# main.net
KiCad netlist of a schematic drawn in Altium Designer
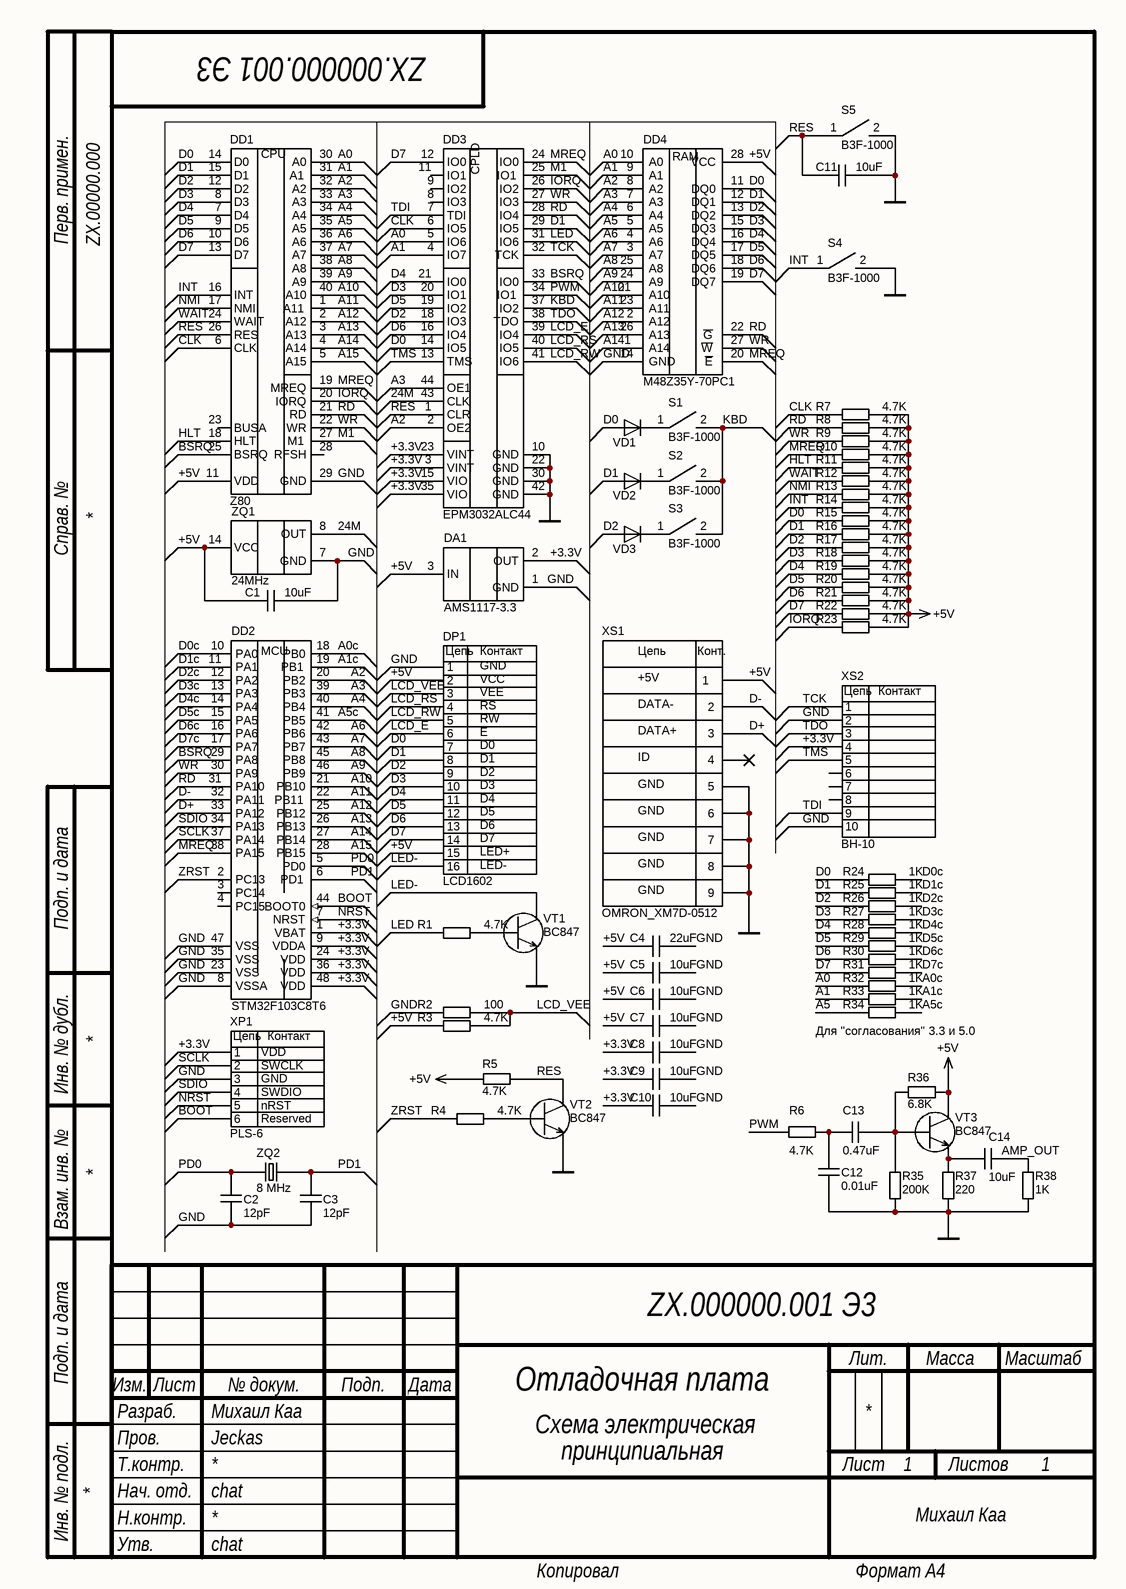
[diagram p0: main.SchDoc]

(export (version "E")
  (design (tool "Eeschema 10.0.6"))
  (components
    (comp (ref "C1") (value "10uF") (footprint "C0805") (libsource (lib "Capacitors") (part "CapCer")))
    (comp (ref "C2") (value "12pF") (footprint "C0805") (libsource (lib "Capacitors") (part "CapCer")))
    (comp (ref "C3") (value "12pF") (footprint "C0805") (libsource (lib "Capacitors") (part "CapCer")))
    (comp (ref "C4") (value "22uF") (footprint "С1206") (libsource (lib "Capacitors") (part "CapCer")))
    (comp (ref "C5") (value "10uF") (footprint "C0805") (libsource (lib "Capacitors") (part "CapCer")))
    (comp (ref "C6") (value "10uF") (footprint "C0805") (libsource (lib "Capacitors") (part "CapCer")))
    (comp (ref "C7") (value "10uF") (footprint "C0805") (libsource (lib "Capacitors") (part "CapCer")))
    (comp (ref "C8") (value "10uF") (footprint "C0805") (libsource (lib "Capacitors") (part "CapCer")))
    (comp (ref "C9") (value "10uF") (footprint "C0805") (libsource (lib "Capacitors") (part "CapCer")))
    (comp (ref "C10") (value "10uF") (footprint "C0805") (libsource (lib "Capacitors") (part "CapCer")))
    (comp (ref "C11") (value "10uF") (footprint "C0805") (libsource (lib "Capacitors") (part "CapCer")))
    (comp (ref "C12") (value "0.01uF") (footprint "C0805") (libsource (lib "Capacitors") (part "CapCer")))
    (comp (ref "C13") (value "0.47uF") (footprint "C0805") (libsource (lib "Capacitors") (part "CapCer")))
    (comp (ref "C14") (value "10uF") (footprint "C0805") (libsource (lib "Capacitors") (part "CapCer")))
    (comp (ref "DA1")
      (value "AMS1117-3.3")
      (footprint "SOT229P700X180-4N")
      (libsource (lib "LDO") (part "AMS1117-3.3"))
    )
    (comp (ref "DD1")
      (value "Z80")
      (footprint "DIP1540W47P254L5320H635Q40B")
      (libsource (lib "Z80") (part "Z80"))
    )
    (comp (ref "DD2")
      (value "STM32F103C8T6")
      (footprint "QFP50P900X900X160-48N")
      (description "ARMÂ® CortexÂ®-M3 STM32F1 Microcontroller IC 32-Bit 72MHz 64KB (64K x 8) FLASH 48-LQFP (7x7)")
      (fields (field (name "MF") "STMicroelectronics"))
      (libsource (lib "MCU") (part "STM32F103C8T6"))
    )
    (comp (ref "DD3")
      (value "EPM3032ALC44")
      (footprint "PLCC-44-R")
      (description "44-Pin PLCC44")
      (libsource (lib "cpld") (part "EPM3032ALC44"))
    )
    (comp (ref "DD4")
      (value "M48Z35Y-70PC1")
      (footprint "DIP254P1524X965-28")
      (description "NVSRAM (Non-Volatile SRAM) Memory IC 256Kb (32K x 8) Parallel 70ns 28-PCDIP, CAPHATÂ®")
      (fields (field (name "MF") "STMicroelectronics"))
      (libsource (lib "RAM") (part "M48Z35Y-70PC1"))
    )
    (comp (ref "DP1") (value "LCD1602") (footprint "LCD1602") (libsource (lib "Display") (part "LCD1602")))
    (comp (ref "R1") (value "4.7K") (footprint "R0805") (libsource (lib "Resistors") (part "Res")))
    (comp (ref "R2") (value "100") (footprint "R0805") (libsource (lib "Resistors") (part "Res")))
    (comp (ref "R3") (value "4.7K") (footprint "R0805") (libsource (lib "Resistors") (part "Res")))
    (comp (ref "R4") (value "4.7K") (footprint "R0805") (libsource (lib "Resistors") (part "Res")))
    (comp (ref "R5") (value "4.7K") (footprint "R0805") (libsource (lib "Resistors") (part "Res")))
    (comp (ref "R6") (value "4.7K") (footprint "R0805") (libsource (lib "Resistors") (part "Res")))
    (comp (ref "R7") (value "4.7K") (footprint "R0805") (libsource (lib "Resistors") (part "Res")))
    (comp (ref "R8") (value "4.7K") (footprint "R0805") (libsource (lib "Resistors") (part "Res")))
    (comp (ref "R9") (value "4.7K") (footprint "R0805") (libsource (lib "Resistors") (part "Res")))
    (comp (ref "R10") (value "4.7K") (footprint "R0805") (libsource (lib "Resistors") (part "Res")))
    (comp (ref "R11") (value "4.7K") (footprint "R0805") (libsource (lib "Resistors") (part "Res")))
    (comp (ref "R12") (value "4.7K") (footprint "R0805") (libsource (lib "Resistors") (part "Res")))
    (comp (ref "R13") (value "4.7K") (footprint "R0805") (libsource (lib "Resistors") (part "Res")))
    (comp (ref "R14") (value "4.7K") (footprint "R0805") (libsource (lib "Resistors") (part "Res")))
    (comp (ref "R15") (value "4.7K") (footprint "R0805") (libsource (lib "Resistors") (part "Res")))
    (comp (ref "R16") (value "4.7K") (footprint "R0805") (libsource (lib "Resistors") (part "Res")))
    (comp (ref "R17") (value "4.7K") (footprint "R0805") (libsource (lib "Resistors") (part "Res")))
    (comp (ref "R18") (value "4.7K") (footprint "R0805") (libsource (lib "Resistors") (part "Res")))
    (comp (ref "R19") (value "4.7K") (footprint "R0805") (libsource (lib "Resistors") (part "Res")))
    (comp (ref "R20") (value "4.7K") (footprint "R0805") (libsource (lib "Resistors") (part "Res")))
    (comp (ref "R21") (value "4.7K") (footprint "R0805") (libsource (lib "Resistors") (part "Res")))
    (comp (ref "R22") (value "4.7K") (footprint "R0805") (libsource (lib "Resistors") (part "Res")))
    (comp (ref "R23") (value "4.7K") (footprint "R0805") (libsource (lib "Resistors") (part "Res")))
    (comp (ref "R24") (value "1K") (footprint "R0805") (libsource (lib "Resistors") (part "Res")))
    (comp (ref "R25") (value "1K") (footprint "R0805") (libsource (lib "Resistors") (part "Res")))
    (comp (ref "R26") (value "1K") (footprint "R0805") (libsource (lib "Resistors") (part "Res")))
    (comp (ref "R27") (value "1K") (footprint "R0805") (libsource (lib "Resistors") (part "Res")))
    (comp (ref "R28") (value "1K") (footprint "R0805") (libsource (lib "Resistors") (part "Res")))
    (comp (ref "R29") (value "1K") (footprint "R0805") (libsource (lib "Resistors") (part "Res")))
    (comp (ref "R30") (value "1K") (footprint "R0805") (libsource (lib "Resistors") (part "Res")))
    (comp (ref "R31") (value "1K") (footprint "R0805") (libsource (lib "Resistors") (part "Res")))
    (comp (ref "R32") (value "1K") (footprint "R0805") (libsource (lib "Resistors") (part "Res")))
    (comp (ref "R33") (value "1K") (footprint "R0805") (libsource (lib "Resistors") (part "Res")))
    (comp (ref "R34") (value "1K") (footprint "R0805") (libsource (lib "Resistors") (part "Res")))
    (comp (ref "R35") (value "200K") (footprint "R0805") (libsource (lib "Resistors") (part "Res")))
    (comp (ref "R36") (value "6.8K") (footprint "R0805") (libsource (lib "Resistors") (part "Res")))
    (comp (ref "R37") (value "220") (footprint "R0805") (libsource (lib "Resistors") (part "Res")))
    (comp (ref "R38") (value "1K") (footprint "R0805") (libsource (lib "Resistors") (part "Res")))
    (comp (ref "S1")
      (value "B3F-1000")
      (footprint "SW_B3F-1000")
      (libsource (lib "Buttons") (part "B3F-1000"))
    )
    (comp (ref "S2")
      (value "B3F-1000")
      (footprint "SW_B3F-1000")
      (libsource (lib "Buttons") (part "B3F-1000"))
    )
    (comp (ref "S3")
      (value "B3F-1000")
      (footprint "SW_B3F-1000")
      (libsource (lib "Buttons") (part "B3F-1000"))
    )
    (comp (ref "S4")
      (value "B3F-1000")
      (footprint "SW_B3F-1000")
      (libsource (lib "Buttons") (part "B3F-1000"))
    )
    (comp (ref "S5")
      (value "B3F-1000")
      (footprint "SW_B3F-1000")
      (libsource (lib "Buttons") (part "B3F-1000"))
    )
    (comp (ref "VD1")
      (value "1N4148W")
      (footprint "SODFL1608X70N")
      (libsource (lib "Diodes") (part "1N4148W"))
    )
    (comp (ref "VD2")
      (value "1N4148W")
      (footprint "SODFL1608X70N")
      (libsource (lib "Diodes") (part "1N4148W"))
    )
    (comp (ref "VD3")
      (value "1N4148W")
      (footprint "SODFL1608X70N")
      (libsource (lib "Diodes") (part "1N4148W"))
    )
    (comp (ref "VT1")
      (value "BC847")
      (footprint "BC847")
      (description "NPN Transistor")
      (libsource (lib "Transistors") (part "BC847"))
    )
    (comp (ref "VT2")
      (value "BC847")
      (footprint "BC847")
      (description "NPN Transistor")
      (libsource (lib "Transistors") (part "BC847"))
    )
    (comp (ref "VT3")
      (value "BC847")
      (footprint "BC847")
      (description "NPN Transistor")
      (libsource (lib "Transistors") (part "BC847"))
    )
    (comp (ref "XP1") (value "PLS-6") (footprint "6pin") (libsource (lib "Connectors") (part "PLS-6")))
    (comp (ref "XS1")
      (value "OMRON_XM7D-0512")
      (footprint "OMRON_XM7D-0512")
      (libsource (lib "Connectors") (part "OMRON_XM7D-0512"))
    )
    (comp (ref "XS2")
      (value "BH-10")
      (footprint "BH-10")
      (description "10 Position Total Dual Row 2.54 mm Pitch Straight Male Shrouded Box Header")
      (fields (field (name "MF") "Sullins Connector") (field (name "MP") "SBH11-PBPC-D05-ST-BK"))
      (libsource (lib "Connectors") (part "BH-10"))
    )
    (comp (ref "ZQ1")
      (value "24MHz")
      (footprint "OSC_ECS-100A-240")
      (description "Oscillator  14-DIP, 4 Leads (Full Size, Metal Can)")
      (fields (field (name "MP") "ECS-100A-240"))
      (libsource (lib "Oscillators") (part "ECS-100A-240"))
    )
    (comp (ref "ZQ2")
      (value "8 MHz")
      (footprint "XTAL_ECS-80-S-4")
      (libsource (lib "Oscillators") (part "HC-49S_8M"))
    )
  )
  (nets
    (net (code "1") (name "+5V") (class "Default")
      (node (ref "C1") (pin "1") (pinfunction "1_1") (pintype "passive"))
      (node (ref "C4") (pin "1") (pinfunction "1_1") (pintype "passive"))
      (node (ref "C5") (pin "1") (pinfunction "1_1") (pintype "passive"))
      (node (ref "C6") (pin "1") (pinfunction "1_1") (pintype "passive"))
      (node (ref "C7") (pin "1") (pinfunction "1_1") (pintype "passive"))
      (node (ref "DA1") (pin "3") (pinfunction "IN_3") (pintype "passive"))
      (node (ref "DD1") (pin "11") (pinfunction "VDD_11") (pintype "passive"))
      (node (ref "DD4") (pin "28") (pinfunction "VCC_28") (pintype "passive"))
      (node (ref "DP1") (pin "15") (pinfunction "15_15") (pintype "passive"))
      (node (ref "DP1") (pin "2") (pinfunction "2_2") (pintype "passive"))
      (node (ref "R10") (pin "2") (pinfunction "2_2") (pintype "passive"))
      (node (ref "R11") (pin "2") (pinfunction "2_2") (pintype "passive"))
      (node (ref "R12") (pin "2") (pinfunction "2_2") (pintype "passive"))
      (node (ref "R13") (pin "2") (pinfunction "2_2") (pintype "passive"))
      (node (ref "R14") (pin "2") (pinfunction "2_2") (pintype "passive"))
      (node (ref "R15") (pin "2") (pinfunction "2_2") (pintype "passive"))
      (node (ref "R16") (pin "2") (pinfunction "2_2") (pintype "passive"))
      (node (ref "R17") (pin "2") (pinfunction "2_2") (pintype "passive"))
      (node (ref "R18") (pin "2") (pinfunction "2_2") (pintype "passive"))
      (node (ref "R19") (pin "2") (pinfunction "2_2") (pintype "passive"))
      (node (ref "R20") (pin "2") (pinfunction "2_2") (pintype "passive"))
      (node (ref "R21") (pin "2") (pinfunction "2_2") (pintype "passive"))
      (node (ref "R22") (pin "2") (pinfunction "2_2") (pintype "passive"))
      (node (ref "R23") (pin "2") (pinfunction "2_2") (pintype "passive"))
      (node (ref "R3") (pin "1") (pinfunction "1_1") (pintype "passive"))
      (node (ref "R36") (pin "1") (pinfunction "1_1") (pintype "passive"))
      (node (ref "R5") (pin "2") (pinfunction "2_2") (pintype "passive"))
      (node (ref "R7") (pin "2") (pinfunction "2_2") (pintype "passive"))
      (node (ref "R8") (pin "2") (pinfunction "2_2") (pintype "passive"))
      (node (ref "R9") (pin "2") (pinfunction "2_2") (pintype "passive"))
      (node (ref "VT3") (pin "3") (pinfunction "C_3") (pintype "power_in"))
      (node (ref "XS1") (pin "1") (pinfunction "1_1") (pintype "passive"))
      (node (ref "ZQ1") (pin "14") (pinfunction "VCC_14") (pintype "passive"))
    )
    (net (code "2") (name "/+3.3V") (class "Default")
      (node (ref "C10") (pin "1") (pinfunction "1_1") (pintype "passive"))
      (node (ref "C8") (pin "1") (pinfunction "1_1") (pintype "passive"))
      (node (ref "C9") (pin "1") (pinfunction "1_1") (pintype "passive"))
      (node (ref "DA1") (pin "2") (pinfunction "OUT_2") (pintype "passive"))
      (node (ref "DD2") (pin "1") (pinfunction "VBAT_1") (pintype "bidirectional"))
      (node (ref "DD2") (pin "24") (pinfunction "VDD_24") (pintype "power_in"))
      (node (ref "DD2") (pin "36") (pinfunction "VDD_36") (pintype "power_in"))
      (node (ref "DD2") (pin "48") (pinfunction "VDD_48") (pintype "power_in"))
      (node (ref "DD2") (pin "9") (pinfunction "VDDA_9") (pintype "power_in"))
      (node (ref "DD3") (pin "15") (pinfunction "VIO_15") (pintype "passive"))
      (node (ref "DD3") (pin "23") (pinfunction "VINT_23") (pintype "passive"))
      (node (ref "DD3") (pin "3") (pinfunction "VINT_3") (pintype "passive"))
      (node (ref "DD3") (pin "35") (pinfunction "VIO_35") (pintype "passive"))
      (node (ref "XP1") (pin "1") (pinfunction "1_1") (pintype "passive"))
      (node (ref "XS2") (pin "4") (pinfunction "4_4") (pintype "passive"))
    )
    (net (code "3") (name "/24M") (class "Default")
      (node (ref "DD3") (pin "43") (pinfunction "CLK_43") (pintype "passive"))
      (node (ref "ZQ1") (pin "8") (pinfunction "OUT_8") (pintype "passive"))
    )
    (net (code "4") (name "/A0") (class "Default")
      (node (ref "DD1") (pin "30") (pinfunction "A0_30") (pintype "passive"))
      (node (ref "DD3") (pin "5") (pinfunction "IO6_5") (pintype "passive"))
      (node (ref "DD4") (pin "10") (pinfunction "A0_10") (pintype "passive"))
      (node (ref "R32") (pin "1") (pinfunction "1_1") (pintype "passive"))
    )
    (net (code "5") (name "/A0c") (class "Default")
      (node (ref "DD2") (pin "18") (pinfunction "PB0_18") (pintype "bidirectional"))
      (node (ref "R32") (pin "2") (pinfunction "2_2") (pintype "passive"))
    )
    (net (code "6") (name "/A1") (class "Default")
      (node (ref "DD1") (pin "31") (pinfunction "A1_31") (pintype "passive"))
      (node (ref "DD3") (pin "4") (pinfunction "IO7_4") (pintype "passive"))
      (node (ref "DD4") (pin "9") (pinfunction "A1_9") (pintype "passive"))
      (node (ref "R33") (pin "1") (pinfunction "1_1") (pintype "passive"))
    )
    (net (code "7") (name "/A1c") (class "Default")
      (node (ref "DD2") (pin "19") (pinfunction "PB1_19") (pintype "bidirectional"))
      (node (ref "R33") (pin "2") (pinfunction "2_2") (pintype "passive"))
    )
    (net (code "8") (name "/A2") (class "Default")
      (node (ref "DD1") (pin "32") (pinfunction "A2_32") (pintype "passive"))
      (node (ref "DD2") (pin "20") (pinfunction "PB2_20") (pintype "bidirectional"))
      (node (ref "DD3") (pin "2") (pinfunction "OE2_2") (pintype "passive"))
      (node (ref "DD4") (pin "8") (pinfunction "A2_8") (pintype "passive"))
    )
    (net (code "9") (name "/A3") (class "Default")
      (node (ref "DD1") (pin "33") (pinfunction "A3_33") (pintype "passive"))
      (node (ref "DD2") (pin "39") (pinfunction "PB3_39") (pintype "bidirectional"))
      (node (ref "DD3") (pin "44") (pinfunction "OE1_44") (pintype "passive"))
      (node (ref "DD4") (pin "7") (pinfunction "A3_7") (pintype "passive"))
    )
    (net (code "10") (name "/A4") (class "Default")
      (node (ref "DD1") (pin "34") (pinfunction "A4_34") (pintype "passive"))
      (node (ref "DD2") (pin "40") (pinfunction "PB4_40") (pintype "bidirectional"))
      (node (ref "DD4") (pin "6") (pinfunction "A4_6") (pintype "passive"))
    )
    (net (code "11") (name "/A5") (class "Default")
      (node (ref "DD1") (pin "35") (pinfunction "A5_35") (pintype "passive"))
      (node (ref "DD4") (pin "5") (pinfunction "A5_5") (pintype "passive"))
      (node (ref "R34") (pin "1") (pinfunction "1_1") (pintype "passive"))
    )
    (net (code "12") (name "/A5c") (class "Default")
      (node (ref "DD2") (pin "41") (pinfunction "PB5_41") (pintype "bidirectional"))
      (node (ref "R34") (pin "2") (pinfunction "2_2") (pintype "passive"))
    )
    (net (code "13") (name "/A6") (class "Default")
      (node (ref "DD1") (pin "36") (pinfunction "A6_36") (pintype "passive"))
      (node (ref "DD2") (pin "42") (pinfunction "PB6_42") (pintype "bidirectional"))
      (node (ref "DD4") (pin "4") (pinfunction "A6_4") (pintype "passive"))
    )
    (net (code "14") (name "/A7") (class "Default")
      (node (ref "DD1") (pin "37") (pinfunction "A7_37") (pintype "passive"))
      (node (ref "DD2") (pin "43") (pinfunction "PB7_43") (pintype "bidirectional"))
      (node (ref "DD4") (pin "3") (pinfunction "A7_3") (pintype "passive"))
    )
    (net (code "15") (name "/A8") (class "Default")
      (node (ref "DD1") (pin "38") (pinfunction "A8_38") (pintype "passive"))
      (node (ref "DD2") (pin "45") (pinfunction "PB8_45") (pintype "bidirectional"))
      (node (ref "DD4") (pin "25") (pinfunction "A8_25") (pintype "passive"))
    )
    (net (code "16") (name "/A9") (class "Default")
      (node (ref "DD1") (pin "39") (pinfunction "A9_39") (pintype "passive"))
      (node (ref "DD2") (pin "46") (pinfunction "PB9_46") (pintype "bidirectional"))
      (node (ref "DD4") (pin "24") (pinfunction "A9_24") (pintype "passive"))
    )
    (net (code "17") (name "/A10") (class "Default")
      (node (ref "DD1") (pin "40") (pinfunction "A10_40") (pintype "passive"))
      (node (ref "DD2") (pin "21") (pinfunction "PB10_21") (pintype "bidirectional"))
      (node (ref "DD4") (pin "21") (pinfunction "A10_21") (pintype "passive"))
    )
    (net (code "18") (name "/A11") (class "Default")
      (node (ref "DD1") (pin "1") (pinfunction "A11_1") (pintype "passive"))
      (node (ref "DD2") (pin "22") (pinfunction "PB11_22") (pintype "bidirectional"))
      (node (ref "DD4") (pin "23") (pinfunction "A11_23") (pintype "passive"))
    )
    (net (code "19") (name "/A12") (class "Default")
      (node (ref "DD1") (pin "2") (pinfunction "A12_2") (pintype "passive"))
      (node (ref "DD2") (pin "25") (pinfunction "PB12_25") (pintype "bidirectional"))
      (node (ref "DD4") (pin "2") (pinfunction "A12_2") (pintype "passive"))
    )
    (net (code "20") (name "/A13") (class "Default")
      (node (ref "DD1") (pin "3") (pinfunction "A13_3") (pintype "passive"))
      (node (ref "DD2") (pin "26") (pinfunction "PB13_26") (pintype "bidirectional"))
      (node (ref "DD4") (pin "26") (pinfunction "A13_26") (pintype "passive"))
    )
    (net (code "21") (name "/A14") (class "Default")
      (node (ref "DD1") (pin "4") (pinfunction "A14_4") (pintype "passive"))
      (node (ref "DD2") (pin "27") (pinfunction "PB14_27") (pintype "bidirectional"))
      (node (ref "DD4") (pin "1") (pinfunction "A14_1") (pintype "passive"))
    )
    (net (code "22") (name "/A15") (class "Default")
      (node (ref "DD1") (pin "5") (pinfunction "A15_5") (pintype "passive"))
      (node (ref "DD2") (pin "28") (pinfunction "PB15_28") (pintype "bidirectional"))
    )
    (net (code "23") (name "/AMP_OUT") (class "Default")
      (node (ref "C14") (pin "2") (pinfunction "2_2") (pintype "passive"))
      (node (ref "R38") (pin "1") (pinfunction "1_1") (pintype "passive"))
    )
    (net (code "24") (name "/BOOT") (class "Default")
      (node (ref "DD2") (pin "44") (pinfunction "BOOT0_44") (pintype "input"))
      (node (ref "XP1") (pin "6") (pinfunction "6_6") (pintype "passive"))
    )
    (net (code "25") (name "/BSRQ") (class "Default")
      (node (ref "DD1") (pin "25") (pinfunction "BSRQ_25") (pintype "passive"))
      (node (ref "DD2") (pin "29") (pinfunction "PA8_29") (pintype "bidirectional"))
      (node (ref "DD3") (pin "33") (pinfunction "IO0_33") (pintype "passive"))
    )
    (net (code "26") (name "/CLK") (class "Default")
      (node (ref "DD1") (pin "6") (pinfunction "CLK_6") (pintype "passive"))
      (node (ref "DD3") (pin "6") (pinfunction "IO5_6") (pintype "passive"))
      (node (ref "R7") (pin "1") (pinfunction "1_1") (pintype "passive"))
    )
    (net (code "27") (name "/D+") (class "Default")
      (node (ref "DD2") (pin "33") (pinfunction "PA12_33") (pintype "bidirectional"))
      (node (ref "XS1") (pin "3") (pinfunction "3_3") (pintype "passive"))
    )
    (net (code "28") (name "/D-") (class "Default")
      (node (ref "DD2") (pin "32") (pinfunction "PA11_32") (pintype "bidirectional"))
      (node (ref "XS1") (pin "2") (pinfunction "2_2") (pintype "passive"))
    )
    (net (code "29") (name "/D0") (class "Default")
      (node (ref "DD1") (pin "14") (pinfunction "D0_14") (pintype "passive"))
      (node (ref "DD3") (pin "14") (pinfunction "IO5_14") (pintype "passive"))
      (node (ref "DD4") (pin "11") (pinfunction "DQ0_11") (pintype "passive"))
      (node (ref "DP1") (pin "7") (pinfunction "7_7") (pintype "passive"))
      (node (ref "R15") (pin "1") (pinfunction "1_1") (pintype "passive"))
      (node (ref "R24") (pin "1") (pinfunction "1_1") (pintype "passive"))
      (node (ref "VD1") (pin "A") (pinfunction "A_A") (pintype "passive"))
    )
    (net (code "30") (name "/D0c") (class "Default")
      (node (ref "DD2") (pin "10") (pinfunction "PA0_10") (pintype "bidirectional"))
      (node (ref "R24") (pin "2") (pinfunction "2_2") (pintype "passive"))
    )
    (net (code "31") (name "/D1") (class "Default")
      (node (ref "DD1") (pin "15") (pinfunction "D1_15") (pintype "passive"))
      (node (ref "DD3") (pin "29") (pinfunction "IO5_29") (pintype "passive"))
      (node (ref "DD4") (pin "12") (pinfunction "DQ1_12") (pintype "passive"))
      (node (ref "DP1") (pin "8") (pinfunction "8_8") (pintype "passive"))
      (node (ref "R16") (pin "1") (pinfunction "1_1") (pintype "passive"))
      (node (ref "R25") (pin "1") (pinfunction "1_1") (pintype "passive"))
      (node (ref "VD2") (pin "A") (pinfunction "A_A") (pintype "passive"))
    )
    (net (code "32") (name "/D1c") (class "Default")
      (node (ref "DD2") (pin "11") (pinfunction "PA1_11") (pintype "bidirectional"))
      (node (ref "R25") (pin "2") (pinfunction "2_2") (pintype "passive"))
    )
    (net (code "33") (name "/D2") (class "Default")
      (node (ref "DD1") (pin "12") (pinfunction "D2_12") (pintype "passive"))
      (node (ref "DD3") (pin "18") (pinfunction "IO3_18") (pintype "passive"))
      (node (ref "DD4") (pin "13") (pinfunction "DQ2_13") (pintype "passive"))
      (node (ref "DP1") (pin "9") (pinfunction "9_9") (pintype "passive"))
      (node (ref "R17") (pin "1") (pinfunction "1_1") (pintype "passive"))
      (node (ref "R26") (pin "1") (pinfunction "1_1") (pintype "passive"))
      (node (ref "VD3") (pin "A") (pinfunction "A_A") (pintype "passive"))
    )
    (net (code "34") (name "/D2c") (class "Default")
      (node (ref "DD2") (pin "12") (pinfunction "PA2_12") (pintype "bidirectional"))
      (node (ref "R26") (pin "2") (pinfunction "2_2") (pintype "passive"))
    )
    (net (code "35") (name "/D3") (class "Default")
      (node (ref "DD1") (pin "8") (pinfunction "D3_8") (pintype "passive"))
      (node (ref "DD3") (pin "20") (pinfunction "IO1_20") (pintype "passive"))
      (node (ref "DD4") (pin "15") (pinfunction "DQ3_15") (pintype "passive"))
      (node (ref "DP1") (pin "10") (pinfunction "10_10") (pintype "passive"))
      (node (ref "R18") (pin "1") (pinfunction "1_1") (pintype "passive"))
      (node (ref "R27") (pin "1") (pinfunction "1_1") (pintype "passive"))
    )
    (net (code "36") (name "/D3c") (class "Default")
      (node (ref "DD2") (pin "13") (pinfunction "PA3_13") (pintype "bidirectional"))
      (node (ref "R27") (pin "2") (pinfunction "2_2") (pintype "passive"))
    )
    (net (code "37") (name "/D4") (class "Default")
      (node (ref "DD1") (pin "7") (pinfunction "D4_7") (pintype "passive"))
      (node (ref "DD3") (pin "21") (pinfunction "IO0_21") (pintype "passive"))
      (node (ref "DD4") (pin "16") (pinfunction "DQ4_16") (pintype "passive"))
      (node (ref "DP1") (pin "11") (pinfunction "11_11") (pintype "passive"))
      (node (ref "R19") (pin "1") (pinfunction "1_1") (pintype "passive"))
      (node (ref "R28") (pin "1") (pinfunction "1_1") (pintype "passive"))
    )
    (net (code "38") (name "/D4c") (class "Default")
      (node (ref "DD2") (pin "14") (pinfunction "PA4_14") (pintype "bidirectional"))
      (node (ref "R28") (pin "2") (pinfunction "2_2") (pintype "passive"))
    )
    (net (code "39") (name "/D5") (class "Default")
      (node (ref "DD1") (pin "9") (pinfunction "D5_9") (pintype "passive"))
      (node (ref "DD3") (pin "19") (pinfunction "IO2_19") (pintype "passive"))
      (node (ref "DD4") (pin "17") (pinfunction "DQ5_17") (pintype "passive"))
      (node (ref "DP1") (pin "12") (pinfunction "12_12") (pintype "passive"))
      (node (ref "R20") (pin "1") (pinfunction "1_1") (pintype "passive"))
      (node (ref "R29") (pin "1") (pinfunction "1_1") (pintype "passive"))
    )
    (net (code "40") (name "/D5c") (class "Default")
      (node (ref "DD2") (pin "15") (pinfunction "PA5_15") (pintype "bidirectional"))
      (node (ref "R29") (pin "2") (pinfunction "2_2") (pintype "passive"))
    )
    (net (code "41") (name "/D6") (class "Default")
      (node (ref "DD1") (pin "10") (pinfunction "D6_10") (pintype "passive"))
      (node (ref "DD3") (pin "16") (pinfunction "IO4_16") (pintype "passive"))
      (node (ref "DD4") (pin "18") (pinfunction "DQ6_18") (pintype "passive"))
      (node (ref "DP1") (pin "13") (pinfunction "13_13") (pintype "passive"))
      (node (ref "R21") (pin "1") (pinfunction "1_1") (pintype "passive"))
      (node (ref "R30") (pin "1") (pinfunction "1_1") (pintype "passive"))
    )
    (net (code "42") (name "/D6c") (class "Default")
      (node (ref "DD2") (pin "16") (pinfunction "PA6_16") (pintype "bidirectional"))
      (node (ref "R30") (pin "2") (pinfunction "2_2") (pintype "passive"))
    )
    (net (code "43") (name "/D7") (class "Default")
      (node (ref "DD1") (pin "13") (pinfunction "D7_13") (pintype "passive"))
      (node (ref "DD3") (pin "12") (pinfunction "IO0_12") (pintype "passive"))
      (node (ref "DD4") (pin "19") (pinfunction "DQ7_19") (pintype "passive"))
      (node (ref "DP1") (pin "14") (pinfunction "14_14") (pintype "passive"))
      (node (ref "R22") (pin "1") (pinfunction "1_1") (pintype "passive"))
      (node (ref "R31") (pin "1") (pinfunction "1_1") (pintype "passive"))
    )
    (net (code "44") (name "/D7c") (class "Default")
      (node (ref "DD2") (pin "17") (pinfunction "PA7_17") (pintype "bidirectional"))
      (node (ref "R31") (pin "2") (pinfunction "2_2") (pintype "passive"))
    )
    (net (code "45") (name "/HLT") (class "Default")
      (node (ref "DD1") (pin "18") (pinfunction "HLT_18") (pintype "passive"))
      (node (ref "R11") (pin "1") (pinfunction "1_1") (pintype "passive"))
    )
    (net (code "46") (name "/INT") (class "Default")
      (node (ref "DD1") (pin "16") (pinfunction "INT_16") (pintype "passive"))
      (node (ref "R14") (pin "1") (pinfunction "1_1") (pintype "passive"))
      (node (ref "S4") (pin "1") (pinfunction "0_1") (pintype "passive"))
    )
    (net (code "47") (name "/IORQ") (class "Default")
      (node (ref "DD1") (pin "20") (pinfunction "IORQ_20") (pintype "passive"))
      (node (ref "DD3") (pin "26") (pinfunction "IO2_26") (pintype "passive"))
      (node (ref "R23") (pin "1") (pinfunction "1_1") (pintype "passive"))
    )
    (net (code "48") (name "/KBD") (class "Default")
      (node (ref "DD3") (pin "37") (pinfunction "IO2_37") (pintype "passive"))
      (node (ref "S1") (pin "2") (pinfunction "1_2") (pintype "passive"))
      (node (ref "S2") (pin "2") (pinfunction "1_2") (pintype "passive"))
      (node (ref "S3") (pin "2") (pinfunction "1_2") (pintype "passive"))
    )
    (net (code "49") (name "/LCD_E") (class "Default")
      (node (ref "DD3") (pin "39") (pinfunction "IO4_39") (pintype "passive"))
      (node (ref "DP1") (pin "6") (pinfunction "6_6") (pintype "passive"))
    )
    (net (code "50") (name "/LCD_RS") (class "Default")
      (node (ref "DD3") (pin "40") (pinfunction "IO5_40") (pintype "passive"))
      (node (ref "DP1") (pin "4") (pinfunction "4_4") (pintype "passive"))
    )
    (net (code "51") (name "/LCD_RW") (class "Default")
      (node (ref "DD3") (pin "41") (pinfunction "IO6_41") (pintype "passive"))
      (node (ref "DP1") (pin "5") (pinfunction "5_5") (pintype "passive"))
    )
    (net (code "52") (name "/LCD_VEE") (class "Default")
      (node (ref "DP1") (pin "3") (pinfunction "3_3") (pintype "passive"))
      (node (ref "R2") (pin "2") (pinfunction "2_2") (pintype "passive"))
      (node (ref "R3") (pin "2") (pinfunction "2_2") (pintype "passive"))
    )
    (net (code "53") (name "/LED") (class "Default")
      (node (ref "DD3") (pin "31") (pinfunction "IO6_31") (pintype "passive"))
      (node (ref "R1") (pin "1") (pinfunction "1_1") (pintype "passive"))
    )
    (net (code "54") (name "/LED-") (class "Default")
      (node (ref "DP1") (pin "16") (pinfunction "16_16") (pintype "passive"))
      (node (ref "VT1") (pin "3") (pinfunction "C_3") (pintype "power_in"))
    )
    (net (code "55") (name "/M1") (class "Default")
      (node (ref "DD1") (pin "27") (pinfunction "M1_27") (pintype "passive"))
      (node (ref "DD3") (pin "25") (pinfunction "IO1_25") (pintype "passive"))
    )
    (net (code "56") (name "/MREQ") (class "Default")
      (node (ref "DD1") (pin "19") (pinfunction "MREQ_19") (pintype "passive"))
      (node (ref "DD2") (pin "38") (pinfunction "PA15_38") (pintype "bidirectional"))
      (node (ref "DD3") (pin "24") (pinfunction "IO0_24") (pintype "passive"))
      (node (ref "DD4") (pin "20") (pinfunction "~{E}_20") (pintype "passive"))
      (node (ref "R10") (pin "1") (pinfunction "1_1") (pintype "passive"))
    )
    (net (code "57") (name "/NMI") (class "Default")
      (node (ref "DD1") (pin "17") (pinfunction "NMI_17") (pintype "passive"))
      (node (ref "R13") (pin "1") (pinfunction "1_1") (pintype "passive"))
    )
    (net (code "58") (name "/NRST") (class "Default")
      (node (ref "DD2") (pin "7") (pinfunction "NRST_7") (pintype "input"))
      (node (ref "XP1") (pin "5") (pinfunction "5_5") (pintype "passive"))
    )
    (net (code "59") (name "/PD0") (class "Default")
      (node (ref "C2") (pin "2") (pinfunction "2_2") (pintype "passive"))
      (node (ref "DD2") (pin "5") (pinfunction "PD0_5") (pintype "bidirectional"))
      (node (ref "ZQ2") (pin "2") (pinfunction "2_2") (pintype "passive"))
    )
    (net (code "60") (name "/PD1") (class "Default")
      (node (ref "C3") (pin "2") (pinfunction "2_2") (pintype "passive"))
      (node (ref "DD2") (pin "6") (pinfunction "PD1_6") (pintype "bidirectional"))
      (node (ref "ZQ2") (pin "1") (pinfunction "1_1") (pintype "passive"))
    )
    (net (code "61") (name "/PWM") (class "Default")
      (node (ref "DD3") (pin "34") (pinfunction "IO1_34") (pintype "passive"))
      (node (ref "R6") (pin "1") (pinfunction "1_1") (pintype "passive"))
    )
    (net (code "62") (name "/RD") (class "Default")
      (node (ref "DD1") (pin "21") (pinfunction "RD_21") (pintype "passive"))
      (node (ref "DD2") (pin "31") (pinfunction "PA10_31") (pintype "bidirectional"))
      (node (ref "DD3") (pin "28") (pinfunction "IO4_28") (pintype "passive"))
      (node (ref "DD4") (pin "22") (pinfunction "~{G}_22") (pintype "passive"))
      (node (ref "R8") (pin "1") (pinfunction "1_1") (pintype "passive"))
    )
    (net (code "63") (name "/RES") (class "Default")
      (node (ref "C11") (pin "1") (pinfunction "1_1") (pintype "passive"))
      (node (ref "DD1") (pin "26") (pinfunction "RES_26") (pintype "passive"))
      (node (ref "DD3") (pin "1") (pinfunction "CLR_1") (pintype "passive"))
      (node (ref "R5") (pin "1") (pinfunction "1_1") (pintype "passive"))
      (node (ref "S5") (pin "1") (pinfunction "0_1") (pintype "passive"))
      (node (ref "VT2") (pin "3") (pinfunction "C_3") (pintype "power_in"))
    )
    (net (code "64") (name "/SCLK") (class "Default")
      (node (ref "DD2") (pin "37") (pinfunction "PA14_37") (pintype "bidirectional"))
      (node (ref "XP1") (pin "2") (pinfunction "2_2") (pintype "passive"))
    )
    (net (code "65") (name "/SDIO") (class "Default")
      (node (ref "DD2") (pin "34") (pinfunction "PA13_34") (pintype "bidirectional"))
      (node (ref "XP1") (pin "4") (pinfunction "4_4") (pintype "passive"))
    )
    (net (code "66") (name "/TCK") (class "Default")
      (node (ref "DD3") (pin "32") (pinfunction "TCK_32") (pintype "passive"))
      (node (ref "XS2") (pin "1") (pinfunction "1_1") (pintype "passive"))
    )
    (net (code "67") (name "/TDI") (class "Default")
      (node (ref "DD3") (pin "7") (pinfunction "TDI_7") (pintype "passive"))
      (node (ref "XS2") (pin "9") (pinfunction "9_9") (pintype "passive"))
    )
    (net (code "68") (name "/TDO") (class "Default")
      (node (ref "DD3") (pin "38") (pinfunction "TDO_38") (pintype "passive"))
      (node (ref "XS2") (pin "3") (pinfunction "3_3") (pintype "passive"))
    )
    (net (code "69") (name "/TMS") (class "Default")
      (node (ref "DD3") (pin "13") (pinfunction "TMS_13") (pintype "passive"))
      (node (ref "XS2") (pin "5") (pinfunction "5_5") (pintype "passive"))
    )
    (net (code "70") (name "/WAIT") (class "Default")
      (node (ref "DD1") (pin "24") (pinfunction "WAIT_24") (pintype "passive"))
      (node (ref "R12") (pin "1") (pinfunction "1_1") (pintype "passive"))
    )
    (net (code "71") (name "/WR") (class "Default")
      (node (ref "DD1") (pin "22") (pinfunction "WR_22") (pintype "passive"))
      (node (ref "DD2") (pin "30") (pinfunction "PA9_30") (pintype "bidirectional"))
      (node (ref "DD3") (pin "27") (pinfunction "IO3_27") (pintype "passive"))
      (node (ref "DD4") (pin "27") (pinfunction "~{W}_27") (pintype "passive"))
      (node (ref "R9") (pin "1") (pinfunction "1_1") (pintype "passive"))
    )
    (net (code "72") (name "/ZRST") (class "Default")
      (node (ref "DD2") (pin "2") (pinfunction "PC13_2") (pintype "bidirectional"))
      (node (ref "R4") (pin "1") (pinfunction "1_1") (pintype "passive"))
    )
    (net (code "73") (name "GND") (class "Default")
      (node (ref "C1") (pin "2") (pinfunction "2_2") (pintype "passive"))
      (node (ref "C10") (pin "2") (pinfunction "2_2") (pintype "passive"))
      (node (ref "C11") (pin "2") (pinfunction "2_2") (pintype "passive"))
      (node (ref "C12") (pin "1") (pinfunction "1_1") (pintype "passive"))
      (node (ref "C2") (pin "1") (pinfunction "1_1") (pintype "passive"))
      (node (ref "C3") (pin "1") (pinfunction "1_1") (pintype "passive"))
      (node (ref "C4") (pin "2") (pinfunction "2_2") (pintype "passive"))
      (node (ref "C5") (pin "2") (pinfunction "2_2") (pintype "passive"))
      (node (ref "C6") (pin "2") (pinfunction "2_2") (pintype "passive"))
      (node (ref "C7") (pin "2") (pinfunction "2_2") (pintype "passive"))
      (node (ref "C8") (pin "2") (pinfunction "2_2") (pintype "passive"))
      (node (ref "C9") (pin "2") (pinfunction "2_2") (pintype "passive"))
      (node (ref "DA1") (pin "1") (pinfunction "GND_1") (pintype "passive"))
      (node (ref "DD1") (pin "29") (pinfunction "GND_29") (pintype "passive"))
      (node (ref "DD2") (pin "23") (pinfunction "VSS_23") (pintype "power_in"))
      (node (ref "DD2") (pin "35") (pinfunction "VSS_35") (pintype "power_in"))
      (node (ref "DD2") (pin "47") (pinfunction "VSS_47") (pintype "power_in"))
      (node (ref "DD2") (pin "8") (pinfunction "VSSA_8") (pintype "power_in"))
      (node (ref "DD3") (pin "10") (pinfunction "GND_10") (pintype "passive"))
      (node (ref "DD3") (pin "22") (pinfunction "GND_22") (pintype "passive"))
      (node (ref "DD3") (pin "30") (pinfunction "GND_30") (pintype "passive"))
      (node (ref "DD3") (pin "42") (pinfunction "GND_42") (pintype "passive"))
      (node (ref "DD4") (pin "14") (pinfunction "GND_14") (pintype "passive"))
      (node (ref "DP1") (pin "1") (pinfunction "1_1") (pintype "passive"))
      (node (ref "R2") (pin "1") (pinfunction "1_1") (pintype "passive"))
      (node (ref "R35") (pin "1") (pinfunction "1_1") (pintype "passive"))
      (node (ref "R37") (pin "2") (pinfunction "2_2") (pintype "passive"))
      (node (ref "R38") (pin "2") (pinfunction "2_2") (pintype "passive"))
      (node (ref "S4") (pin "2") (pinfunction "1_2") (pintype "passive"))
      (node (ref "S5") (pin "2") (pinfunction "1_2") (pintype "passive"))
      (node (ref "VT1") (pin "2") (pinfunction "E_2") (pintype "power_in"))
      (node (ref "VT2") (pin "2") (pinfunction "E_2") (pintype "power_in"))
      (node (ref "XP1") (pin "3") (pinfunction "3_3") (pintype "passive"))
      (node (ref "XS1") (pin "5") (pinfunction "5_5") (pintype "passive"))
      (node (ref "XS1") (pin "6") (pinfunction "6_6") (pintype "passive"))
      (node (ref "XS1") (pin "7") (pinfunction "7_7") (pintype "passive"))
      (node (ref "XS1") (pin "8") (pinfunction "8_8") (pintype "passive"))
      (node (ref "XS1") (pin "9") (pinfunction "9_9") (pintype "passive"))
      (node (ref "XS2") (pin "10") (pinfunction "10_10") (pintype "passive"))
      (node (ref "XS2") (pin "2") (pinfunction "2_2") (pintype "passive"))
      (node (ref "ZQ1") (pin "7") (pinfunction "GND_7") (pintype "passive"))
    )
    (net (code "74") (name "Net-(C12-Pad2)") (class "Default")
      (node (ref "C12") (pin "2") (pinfunction "2_2") (pintype "passive"))
      (node (ref "C13") (pin "1") (pinfunction "1_1") (pintype "passive"))
      (node (ref "R6") (pin "2") (pinfunction "2_2") (pintype "passive"))
    )
    (net (code "75") (name "Net-(S1-0)") (class "Default")
      (node (ref "S1") (pin "1") (pinfunction "0_1") (pintype "passive"))
      (node (ref "VD1") (pin "C") (pinfunction "C_C") (pintype "passive"))
    )
    (net (code "76") (name "Net-(S2-0)") (class "Default")
      (node (ref "S2") (pin "1") (pinfunction "0_1") (pintype "passive"))
      (node (ref "VD2") (pin "C") (pinfunction "C_C") (pintype "passive"))
    )
    (net (code "77") (name "Net-(S3-0)") (class "Default")
      (node (ref "S3") (pin "1") (pinfunction "0_1") (pintype "passive"))
      (node (ref "VD3") (pin "C") (pinfunction "C_C") (pintype "passive"))
    )
    (net (code "78") (name "Net-(VT1-B)") (class "Default")
      (node (ref "R1") (pin "2") (pinfunction "2_2") (pintype "passive"))
      (node (ref "VT1") (pin "1") (pinfunction "B_1") (pintype "power_in"))
    )
    (net (code "79") (name "Net-(VT2-B)") (class "Default")
      (node (ref "R4") (pin "2") (pinfunction "2_2") (pintype "passive"))
      (node (ref "VT2") (pin "1") (pinfunction "B_1") (pintype "power_in"))
    )
    (net (code "80") (name "Net-(VT3-B)") (class "Default")
      (node (ref "C13") (pin "2") (pinfunction "2_2") (pintype "passive"))
      (node (ref "R35") (pin "2") (pinfunction "2_2") (pintype "passive"))
      (node (ref "R36") (pin "2") (pinfunction "2_2") (pintype "passive"))
      (node (ref "VT3") (pin "1") (pinfunction "B_1") (pintype "power_in"))
    )
    (net (code "81") (name "Net-(VT3-E)") (class "Default")
      (node (ref "C14") (pin "1") (pinfunction "1_1") (pintype "passive"))
      (node (ref "R37") (pin "1") (pinfunction "1_1") (pintype "passive"))
      (node (ref "VT3") (pin "2") (pinfunction "E_2") (pintype "power_in"))
    )
    (net (code "82") (name "unconnected-(DD1-BUSA-Pad23)") (class "Default")
      (node (ref "DD1") (pin "23") (pinfunction "BUSA_23") (pintype "passive"))
    )
    (net (code "83") (name "unconnected-(DD1-RFSH-Pad28)") (class "Default")
      (node (ref "DD1") (pin "28") (pinfunction "RFSH_28") (pintype "passive"))
    )
    (net (code "84") (name "unconnected-(DD2-PC14-Pad3)") (class "Default")
      (node (ref "DD2") (pin "3") (pinfunction "PC14_3") (pintype "bidirectional"))
    )
    (net (code "85") (name "unconnected-(DD2-PC15-Pad4)") (class "Default")
      (node (ref "DD2") (pin "4") (pinfunction "PC15_4") (pintype "bidirectional"))
    )
    (net (code "86") (name "unconnected-(DD3-IO1-Pad11)") (class "Default")
      (node (ref "DD3") (pin "11") (pinfunction "IO1_11") (pintype "passive"))
    )
    (net (code "87") (name "unconnected-(DD3-IO2-Pad9)") (class "Default")
      (node (ref "DD3") (pin "9") (pinfunction "IO2_9") (pintype "passive"))
    )
    (net (code "88") (name "unconnected-(DD3-IO3-Pad8)") (class "Default")
      (node (ref "DD3") (pin "8") (pinfunction "IO3_8") (pintype "passive"))
    )
    (net (code "89") (name "unconnected-(XS1-Pad4)") (class "Default")
      (node (ref "XS1") (pin "4") (pinfunction "4_4") (pintype "passive+no_connect"))
    )
    (net (code "90") (name "unconnected-(XS2-Pad6)") (class "Default")
      (node (ref "XS2") (pin "6") (pinfunction "6_6") (pintype "passive"))
    )
    (net (code "91") (name "unconnected-(XS2-Pad7)") (class "Default")
      (node (ref "XS2") (pin "7") (pinfunction "7_7") (pintype "passive"))
    )
    (net (code "92") (name "unconnected-(XS2-Pad8)") (class "Default")
      (node (ref "XS2") (pin "8") (pinfunction "8_8") (pintype "passive"))
    )
  )
)
